# Antenna_Supervisory_Circuit.net
KiCad netlist of a schematic drawn in Altium Designer
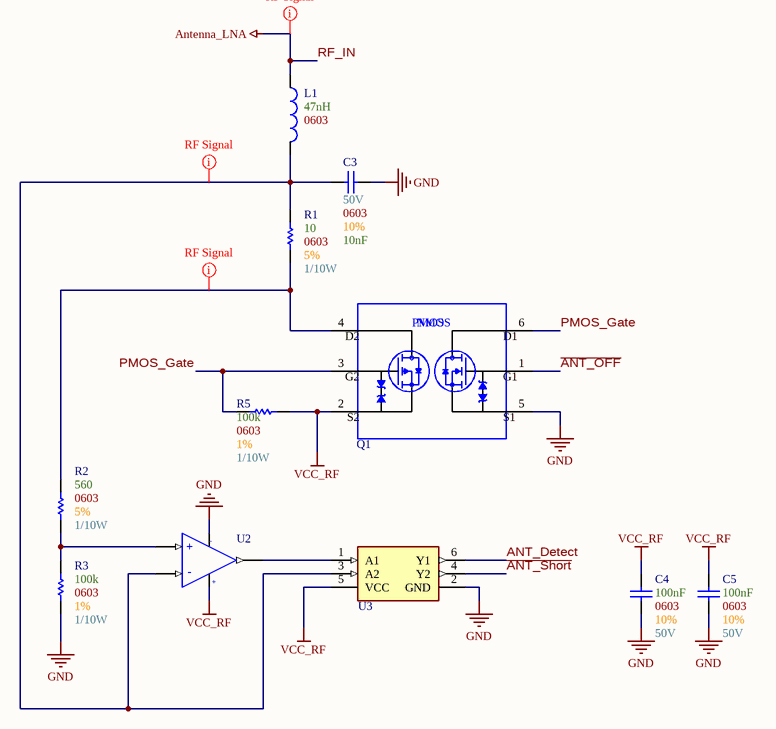
[diagram p0: Antenna Supervisory Circuit.SchDoc]

(export (version "E")
  (design (tool "Eeschema 10.0.6"))
  (components
    (comp (ref "C3")
      (value "[Cap] 0603 0.01uF 10% 50V")
      (footprint "[Cap] SMD 0603")
      (description "C0603C103K5RACTU")
      (fields
        (field (name "MAX VOLTAGE") "50V")
        (field (name "SIZE PACKAGE") "0603")
        (field (name "TOLERANCE") "10%")
        (field (name "CAPACITANCE") "10nF")
      )
      (libsource (lib "Capacitors") (part "[Cap] 0603 0.01uF 10% 50V"))
    )
    (comp (ref "C4")
      (value "[Cap] 0603 0.1uF 10% 50V")
      (footprint "[Cap] SMD 0603")
      (description "CL10B104KB8NNNC")
      (fields
        (field (name "MAX VOLTAGE") "50V")
        (field (name "SIZE PACKAGE") "0603")
        (field (name "TOLERANCE") "10%")
        (field (name "CAPACITANCE") "100nF")
      )
      (libsource (lib "Capacitors") (part "[Cap] 0603 0.1uF 10% 50V"))
    )
    (comp (ref "C5")
      (value "[Cap] 0603 0.1uF 10% 50V")
      (footprint "[Cap] SMD 0603")
      (description "CL10B104KB8NNNC")
      (fields
        (field (name "MAX VOLTAGE") "50V")
        (field (name "SIZE PACKAGE") "0603")
        (field (name "TOLERANCE") "10%")
        (field (name "CAPACITANCE") "100nF")
      )
      (libsource (lib "Capacitors") (part "[Cap] 0603 0.1uF 10% 50V"))
    )
    (comp (ref "L1")
      (value "[47nH] SMD 0603 90mA")
      (footprint "[Inductor] SMD 0603")
      (description "AIMC-0603-47NJ-T")
      (fields (field (name "PACKAGE") "0603") (field (name "INDUCTANCE") "47nH"))
      (libsource (lib "Inductors") (part "[47nH] SMD 0603 90mA"))
    )
    (comp (ref "Q1")
      (value "N/PMOS")
      (footprint "SOT-26")
      (description "DMC2700UDM-7")
      (libsource (lib "Transistors") (part "[NMOS, PMOS] FET Array 20V 1.14A"))
    )
    (comp (ref "R1")
      (value "[10] SMD 0603 5% 1/10W")
      (footprint "[Res] SMD 0603")
      (description "RC0603JR-1310RL")
      (fields
        (field (name "WATTAGE") "1/10W")
        (field (name "TOLERANCE") "5%")
        (field (name "RESISTANCE") "10")
        (field (name "SIZE PACKAGE") "0603")
      )
      (libsource (lib "Resistors") (part "[10] SMD 0603 5% 1/10W"))
    )
    (comp (ref "R2")
      (value "[560] SMD 0603 5% 1/10W")
      (footprint "[Res] SMD 0603")
      (description "RC0603JR-07560RL")
      (fields
        (field (name "WATTAGE") "1/10W")
        (field (name "TOLERANCE") "5%")
        (field (name "RESISTANCE") "560")
        (field (name "SIZE PACKAGE") "0603")
      )
      (libsource (lib "Resistors") (part "[560] SMD 0603 5% 1/10W"))
    )
    (comp (ref "R3")
      (value "[100k] SMD 0603 1% 1/10W")
      (footprint "[Res] SMD 0603")
      (description "RC0603FR-07100KL")
      (fields
        (field (name "WATTAGE") "1/10W")
        (field (name "TOLERANCE") "1%")
        (field (name "RESISTANCE") "100k")
        (field (name "SIZE PACKAGE") "0603")
      )
      (libsource (lib "Resistors") (part "[100k] SMD 0603 1% 1/10W"))
    )
    (comp (ref "R5")
      (value "[100k] SMD 0603 1% 1/10W")
      (footprint "[Res] SMD 0603")
      (description "RC0603FR-07100KL")
      (fields
        (field (name "WATTAGE") "1/10W")
        (field (name "TOLERANCE") "1%")
        (field (name "RESISTANCE") "100k")
        (field (name "SIZE PACKAGE") "0603")
      )
      (libsource (lib "Resistors") (part "[100k] SMD 0603 1% 1/10W"))
    )
    (comp (ref "U2")
      (value "[Op-Amp] Rail-to-Rail Vmax=16V GBP=3kHz")
      (footprint "[Op-Amp] Rail-to-Rail Vmax=16V GBP=3kHz")
      (description "LT6003CS5#TRMPBF")
      (libsource (lib "ICs") (part "[Op-Amp] Rail-to-Rail Vmax=16V GBP=3kHz"))
    )
    (comp (ref "U3")
      (value "[Buffer] Dual Open Drain")
      (footprint "[Buffer] Dual Open Drain")
      (description "NC7WZ07P6X")
      (libsource (lib "ICs") (part "[Buffer] Dual Open Drain"))
    )
  )
  (nets
    (net (code "1") (name "/ANT_Detect") (class "Default")
      (node (ref "U3") (pin "6") (pinfunction "Y1_6") (pintype "output"))
    )
    (net (code "2") (name "/ANT_OFF") (class "Default")
      (node (ref "Q1") (pin "1") (pinfunction "G1_1") (pintype "passive"))
    )
    (net (code "3") (name "/ANT_Short") (class "Default")
      (node (ref "U3") (pin "4") (pinfunction "Y2_4") (pintype "output"))
    )
    (net (code "4") (name "/PMOS_Gate") (class "Default")
      (node (ref "Q1") (pin "3") (pinfunction "G2_3") (pintype "passive"))
      (node (ref "Q1") (pin "6") (pinfunction "D1_6") (pintype "passive"))
      (node (ref "R5") (pin "2") (pinfunction "2_2") (pintype "passive"))
    )
    (net (code "5") (name "Antenna_LNA") (class "Default")
      (node (ref "L1") (pin "1") (pinfunction "1_1") (pintype "passive"))
    )
    (net (code "6") (name "GND") (class "Default")
      (node (ref "C3") (pin "1") (pinfunction "1_1") (pintype "passive"))
      (node (ref "C4") (pin "1") (pinfunction "1_1") (pintype "passive"))
      (node (ref "C5") (pin "1") (pinfunction "1_1") (pintype "passive"))
      (node (ref "Q1") (pin "5") (pinfunction "S1_5") (pintype "passive"))
      (node (ref "R3") (pin "1") (pinfunction "1_1") (pintype "passive"))
      (node (ref "U2") (pin "2") (pinfunction "V-_2") (pintype "power_in"))
      (node (ref "U3") (pin "2") (pinfunction "GND_2") (pintype "power_in"))
    )
    (net (code "7") (name "Net-(Q1-D2)") (class "Default")
      (node (ref "Q1") (pin "4") (pinfunction "D2_4") (pintype "passive"))
      (node (ref "R1") (pin "1") (pinfunction "1_1") (pintype "passive"))
      (node (ref "R2") (pin "2") (pinfunction "2_2") (pintype "passive"))
    )
    (net (code "8") (name "Net-(U2-+IN)") (class "Default")
      (node (ref "R2") (pin "1") (pinfunction "1_1") (pintype "passive"))
      (node (ref "R3") (pin "2") (pinfunction "2_2") (pintype "passive"))
      (node (ref "U2") (pin "3") (pinfunction "+IN_3") (pintype "input"))
    )
    (net (code "9") (name "Net-(U2--IN)") (class "Default")
      (node (ref "C3") (pin "2") (pinfunction "2_2") (pintype "passive"))
      (node (ref "L1") (pin "2") (pinfunction "2_2") (pintype "passive"))
      (node (ref "R1") (pin "2") (pinfunction "2_2") (pintype "passive"))
      (node (ref "U2") (pin "4") (pinfunction "-IN_4") (pintype "input"))
      (node (ref "U3") (pin "3") (pinfunction "A2_3") (pintype "input"))
    )
    (net (code "10") (name "Net-(U2-OUT)") (class "Default")
      (node (ref "U2") (pin "1") (pinfunction "OUT_1") (pintype "output"))
      (node (ref "U3") (pin "1") (pinfunction "A1_1") (pintype "input"))
    )
    (net (code "11") (name "VCC_RF") (class "Default")
      (node (ref "C4") (pin "2") (pinfunction "2_2") (pintype "passive"))
      (node (ref "C5") (pin "2") (pinfunction "2_2") (pintype "passive"))
      (node (ref "Q1") (pin "2") (pinfunction "S2_2") (pintype "passive"))
      (node (ref "R5") (pin "1") (pinfunction "1_1") (pintype "passive"))
      (node (ref "U2") (pin "5") (pinfunction "V+_5") (pintype "power_in"))
      (node (ref "U3") (pin "5") (pinfunction "VCC_5") (pintype "power_in"))
    )
  )
)
